# bracelet.net
KiCad netlist of a schematic drawn in EAGLE
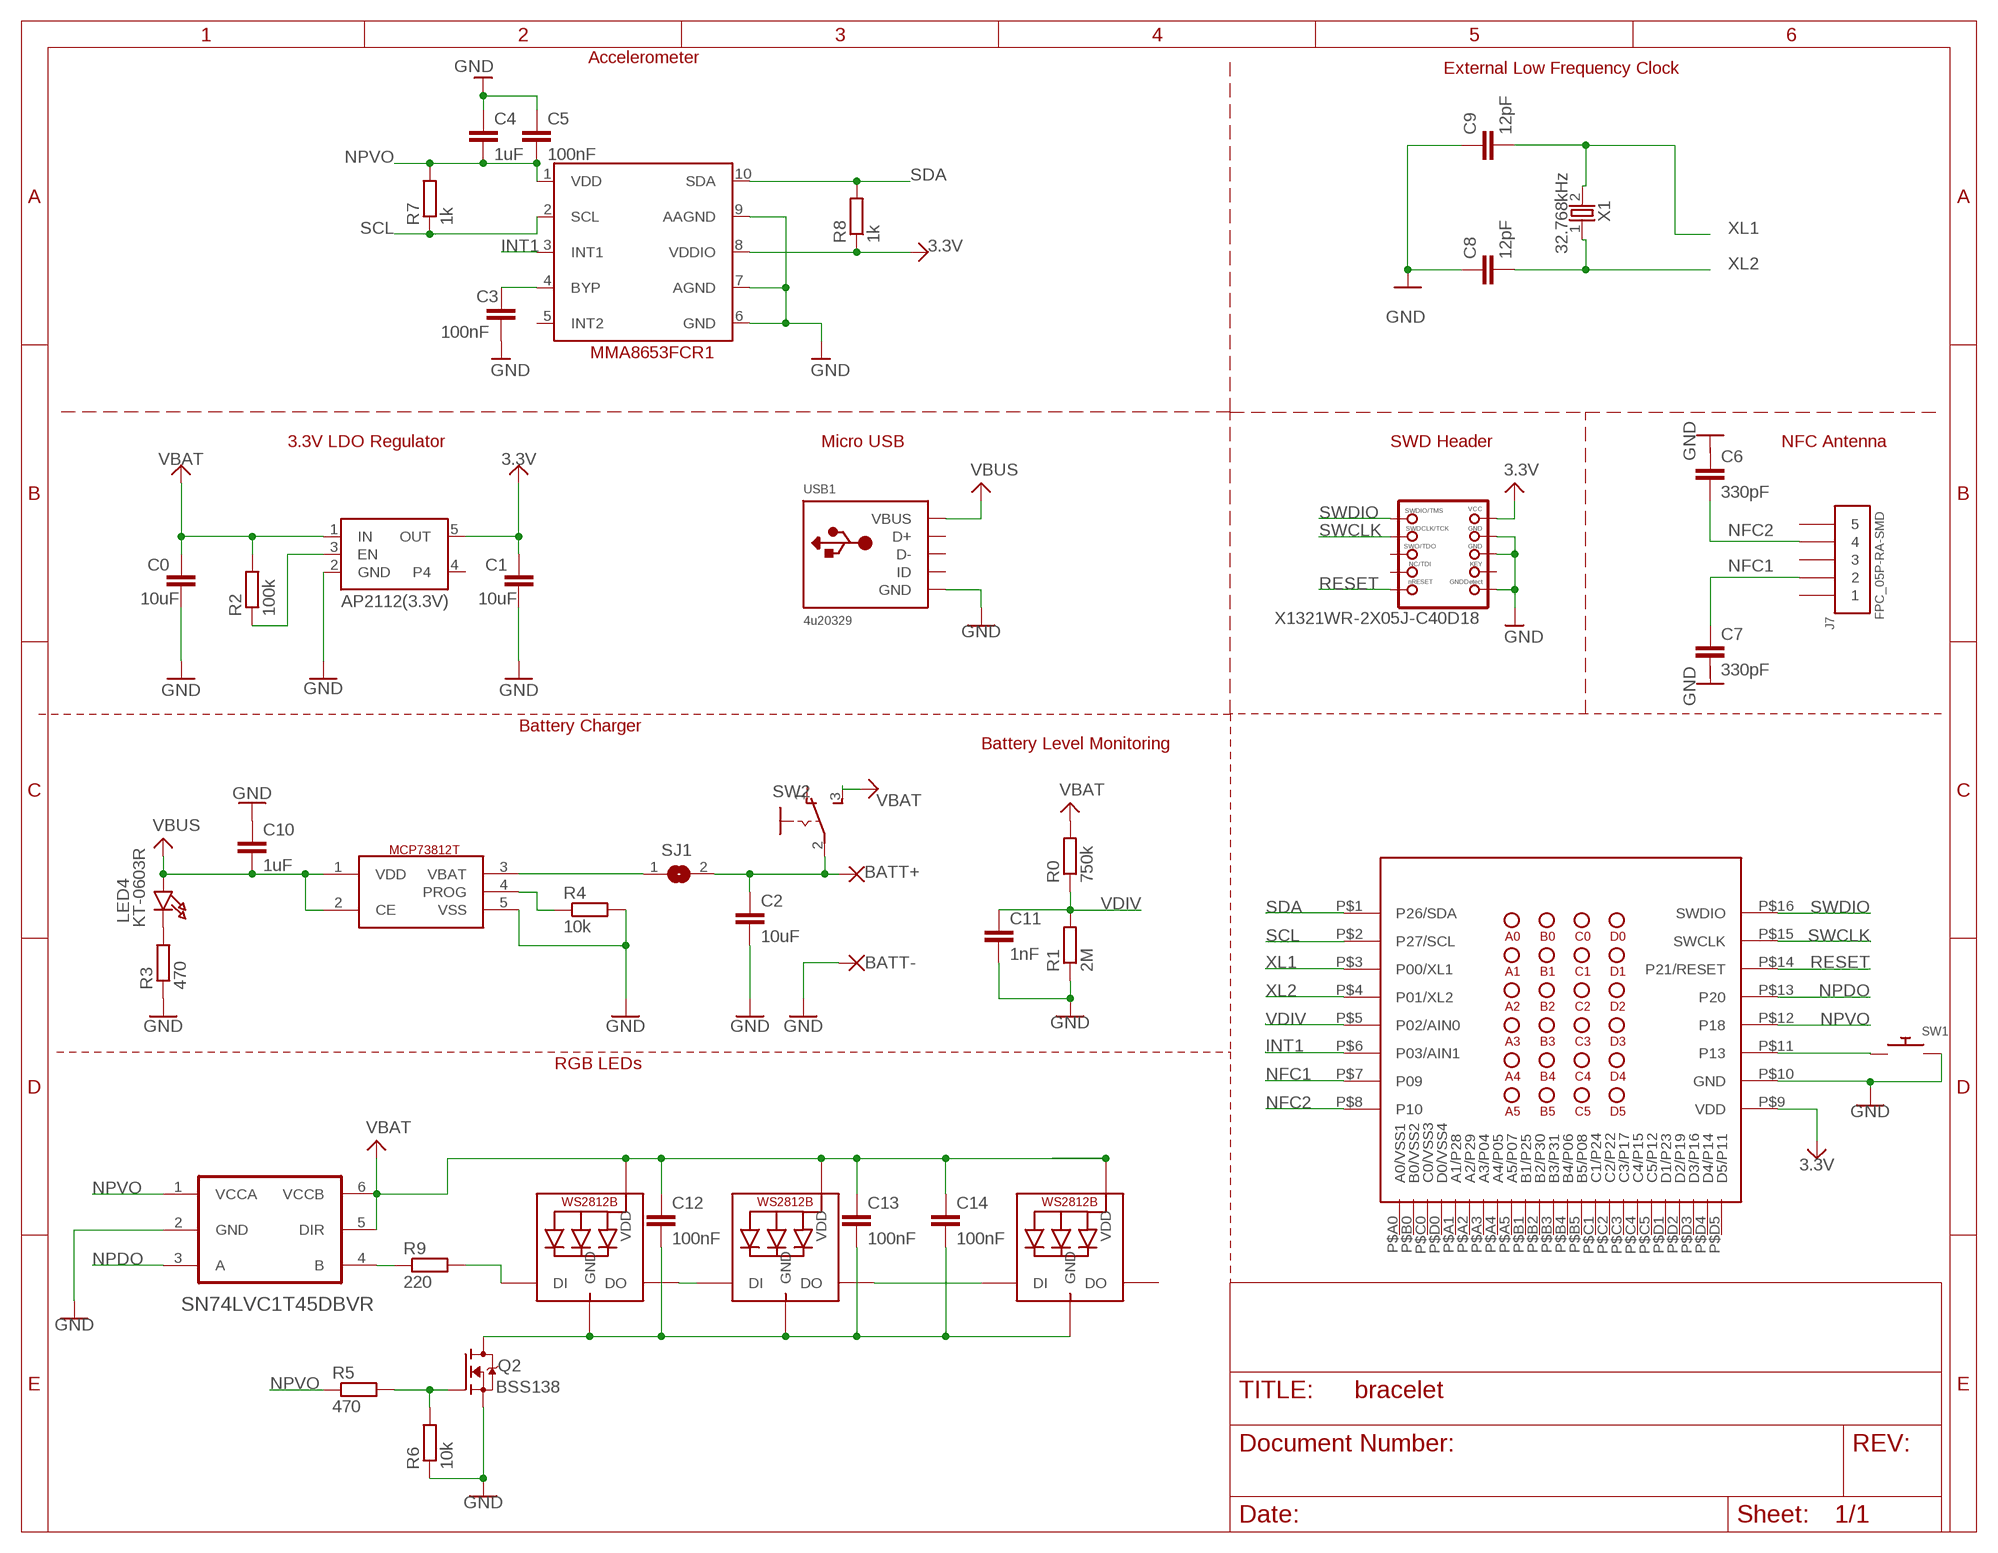
[diagram p0: schematic, sheet 1]

(export (version "E")
  (design (tool "Eeschema 10.0.6"))
  (components
    (comp (ref "BATT+")
      (value "WIREPADSMD2,54-5,08")
      (footprint "eagle-import:SMD2,54-5,08")
      (libsource (lib "eagle-import") (part "WIREPADSMD2,54-5,08"))
    )
    (comp (ref "BATT-")
      (value "WIREPADSMD2,54-5,08")
      (footprint "eagle-import:SMD2,54-5,08")
      (libsource (lib "eagle-import") (part "WIREPADSMD2,54-5,08"))
    )
    (comp (ref "C0")
      (value "10uF")
      (footprint "eagle-import:RESC0402_N")
      (libsource (lib "eagle-import") (part "CAPACITOR_0402_N"))
    )
    (comp (ref "C1")
      (value "10uF")
      (footprint "eagle-import:RESC0402_N")
      (libsource (lib "eagle-import") (part "CAPACITOR_0402_N"))
    )
    (comp (ref "C2")
      (value "10uF")
      (footprint "eagle-import:C0402")
      (libsource (lib "eagle-import") (part "C-EUC0402"))
    )
    (comp (ref "C3")
      (value "100nF")
      (footprint "eagle-import:C0402")
      (libsource (lib "eagle-import") (part "C-EUC0402"))
    )
    (comp (ref "C4")
      (value "1uF")
      (footprint "eagle-import:C0402")
      (libsource (lib "eagle-import") (part "C-EUC0402"))
    )
    (comp (ref "C5")
      (value "100nF")
      (footprint "eagle-import:C0402")
      (libsource (lib "eagle-import") (part "C-EUC0402"))
    )
    (comp (ref "C6")
      (value "330pF")
      (footprint "eagle-import:C0402")
      (libsource (lib "eagle-import") (part "C-EUC0402"))
    )
    (comp (ref "C7")
      (value "330pF")
      (footprint "eagle-import:C0402")
      (libsource (lib "eagle-import") (part "C-EUC0402"))
    )
    (comp (ref "C8")
      (value "12pF")
      (footprint "eagle-import:C0402")
      (libsource (lib "eagle-import") (part "C-EUC0402"))
    )
    (comp (ref "C9")
      (value "12pF")
      (footprint "eagle-import:C0402")
      (libsource (lib "eagle-import") (part "C-EUC0402"))
    )
    (comp (ref "C10")
      (value "1uF")
      (footprint "eagle-import:C0402")
      (libsource (lib "eagle-import") (part "C-EUC0402"))
    )
    (comp (ref "C11")
      (value "1nF")
      (footprint "eagle-import:C0402")
      (libsource (lib "eagle-import") (part "C-EUC0402"))
    )
    (comp (ref "C12")
      (value "100nF")
      (footprint "eagle-import:C0402")
      (libsource (lib "eagle-import") (part "C-EUC0402"))
    )
    (comp (ref "C13")
      (value "100nF")
      (footprint "eagle-import:C0402")
      (libsource (lib "eagle-import") (part "C-EUC0402"))
    )
    (comp (ref "C14")
      (value "100nF")
      (footprint "eagle-import:C0402")
      (libsource (lib "eagle-import") (part "C-EUC0402"))
    )
    (comp (ref "J1")
      (value "X1321WR-2X05J-C40D18")
      (footprint "eagle-import:2X05_1.27MM_BOX_POSTS")
      (libsource (lib "eagle-import") (part "JTAG-CORTEXBOXPOSTS"))
    )
    (comp (ref "J7")
      (value "FPC_05P-RA-SMD")
      (footprint "eagle-import:FPC_05P-RA-SMD")
      (libsource (lib "eagle-import") (part "FPC_05P-RA-SMD"))
    )
    (comp (ref "LED1")
      (value "WS2812B5050")
      (footprint "eagle-import:WS2812B")
      (fields (field (name "MF") "Worldsemi") (field (name "MP") "WS2812B"))
      (libsource (lib "eagle-import") (part "WS2812B5050"))
    )
    (comp (ref "LED2")
      (value "WS2812B5050")
      (footprint "eagle-import:WS2812B")
      (fields (field (name "MF") "Worldsemi") (field (name "MP") "WS2812B"))
      (libsource (lib "eagle-import") (part "WS2812B5050"))
    )
    (comp (ref "LED3")
      (value "WS2812B5050")
      (footprint "eagle-import:WS2812B")
      (fields (field (name "MF") "Worldsemi") (field (name "MP") "WS2812B"))
      (libsource (lib "eagle-import") (part "WS2812B5050"))
    )
    (comp (ref "LED4")
      (value "LED0805_NOOUTLINE")
      (footprint "eagle-import:CHIPLED_0805_NOOUTLINE")
      (libsource (lib "eagle-import") (part "LED0805_NOOUTLINE"))
    )
    (comp (ref "MMA8653FCR1")
      (value "MMA8653FCR1")
      (footprint "eagle-import:MMA8653FCR1")
      (fields (field (name "MF") "NXP Semiconductors"))
      (libsource (lib "eagle-import") (part "MMA8653FCR1"))
    )
    (comp (ref "Q2")
      (value "BSS138")
      (footprint "eagle-import:SOT95P240X111-3N")
      (fields (field (name "MF") "ON Semiconductor"))
      (libsource (lib "eagle-import") (part "BSS138"))
    )
    (comp (ref "R0")
      (value "750k")
      (footprint "eagle-import:R0603")
      (libsource (lib "eagle-import") (part "rcl_334_R-EU_R0603"))
    )
    (comp (ref "R1")
      (value "2M")
      (footprint "eagle-import:R0603")
      (libsource (lib "eagle-import") (part "rcl_334_R-EU_R0603"))
    )
    (comp (ref "R2")
      (value "100k")
      (footprint "eagle-import:R0402")
      (libsource (lib "eagle-import") (part "R-EU_R0402"))
    )
    (comp (ref "R3")
      (value "470")
      (footprint "eagle-import:R0402")
      (libsource (lib "eagle-import") (part "R-EU_R0402"))
    )
    (comp (ref "R4")
      (value "10k")
      (footprint "eagle-import:R0402")
      (libsource (lib "eagle-import") (part "R-EU_R0402"))
    )
    (comp (ref "R5")
      (value "470")
      (footprint "eagle-import:R0402")
      (libsource (lib "eagle-import") (part "R-EU_R0402"))
    )
    (comp (ref "R6")
      (value "10k")
      (footprint "eagle-import:R0402")
      (libsource (lib "eagle-import") (part "R-EU_R0402"))
    )
    (comp (ref "R7")
      (value "1k")
      (footprint "eagle-import:R0402")
      (libsource (lib "eagle-import") (part "R-EU_R0402"))
    )
    (comp (ref "R8")
      (value "1k")
      (footprint "eagle-import:R0402")
      (libsource (lib "eagle-import") (part "R-EU_R0402"))
    )
    (comp (ref "R9")
      (value "220")
      (footprint "eagle-import:R0402")
      (libsource (lib "eagle-import") (part "R-EU_R0402"))
    )
    (comp (ref "SJ1") (value "SJ") (footprint "eagle-import:SJ") (libsource (lib "eagle-import") (part "SJ")))
    (comp (ref "SW1")
      (value "SWITCH_PUSHBUTTONSOFTTOUCHSMD_SJ")
      (footprint "eagle-import:PUSHBUTTON_SMD_SJ")
      (libsource (lib "eagle-import") (part "SWITCH_PUSHBUTTONSOFTTOUCHSMD_SJ"))
    )
    (comp (ref "SW2")
      (value "255SB")
      (footprint "eagle-import:255SB")
      (libsource (lib "eagle-import") (part "255SB"))
    )
    (comp (ref "U$5")
      (value "MCP73812T-420I/OT")
      (footprint "eagle-import:MCP73812T-420I_OT")
      (libsource (lib "eagle-import") (part "MCP73812T-420I/OT"))
    )
    (comp (ref "U1")
      (value "BT832L")
      (footprint "eagle-import:BT832L")
      (libsource (lib "eagle-import") (part "BT832L"))
    )
    (comp (ref "U2")
      (value "SN74LVC1T45DBVR")
      (footprint "eagle-import:SOT95P280X145-6N")
      (fields (field (name "MF") "Texas Instruments"))
      (libsource (lib "eagle-import") (part "SN74LVC1T45DBVR"))
    )
    (comp (ref "U3")
      (value "AP2112(3.3V)")
      (footprint "eagle-import:SOT23-5")
      (libsource (lib "eagle-import") (part "VREG_SOT23-5"))
    )
    (comp (ref "USB1")
      (value "4u20329")
      (footprint "eagle-import:4UCONN_20329_V2")
      (libsource (lib "eagle-import") (part "USB_MICRO_20329_V2"))
    )
    (comp (ref "X1")
      (value "32.768kHz")
      (footprint "eagle-import:XTAL_3215_N")
      (libsource (lib "eagle-import") (part "XTAL_32KHZ"))
    )
  )
  (nets
    (net (code "1") (name "/INT1") (class "Default")
      (node (ref "MMA8653FCR1") (pin "3") (pinfunction "INT1_3") (pintype "bidirectional"))
      (node (ref "U1") (pin "P$6") (pinfunction "P03/AIN1_P$6") (pintype "bidirectional"))
    )
    (net (code "2") (name "/NFC1") (class "Default")
      (node (ref "C7") (pin "1") (pinfunction "1_1") (pintype "passive"))
      (node (ref "J7") (pin "2") (pinfunction "2_2") (pintype "bidirectional"))
      (node (ref "U1") (pin "P$7") (pinfunction "P09_P$7") (pintype "bidirectional"))
    )
    (net (code "3") (name "/NFC2") (class "Default")
      (node (ref "C6") (pin "2") (pinfunction "2_2") (pintype "passive"))
      (node (ref "J7") (pin "4") (pinfunction "4_4") (pintype "bidirectional"))
      (node (ref "U1") (pin "P$8") (pinfunction "P10_P$8") (pintype "bidirectional"))
    )
    (net (code "4") (name "/NPDO") (class "Default")
      (node (ref "U1") (pin "P$13") (pinfunction "P20_P$13") (pintype "bidirectional"))
      (node (ref "U2") (pin "3") (pinfunction "A_3") (pintype "input"))
    )
    (net (code "5") (name "/NPVO") (class "Default")
      (node (ref "C4") (pin "2") (pinfunction "2_2") (pintype "passive"))
      (node (ref "C5") (pin "2") (pinfunction "2_2") (pintype "passive"))
      (node (ref "MMA8653FCR1") (pin "1") (pinfunction "VDD_1") (pintype "bidirectional"))
      (node (ref "R5") (pin "1") (pinfunction "1_1") (pintype "passive"))
      (node (ref "R7") (pin "2") (pinfunction "2_2") (pintype "passive"))
      (node (ref "U1") (pin "P$12") (pinfunction "P18_P$12") (pintype "bidirectional"))
      (node (ref "U2") (pin "1") (pinfunction "VCCA_1") (pintype "power_in"))
    )
    (net (code "6") (name "/RESET") (class "Default")
      (node (ref "J1") (pin "10") (pinfunction "NRESET_10") (pintype "bidirectional"))
      (node (ref "U1") (pin "P$14") (pinfunction "P21/RESET_P$14") (pintype "bidirectional"))
    )
    (net (code "7") (name "/SCL") (class "Default")
      (node (ref "MMA8653FCR1") (pin "2") (pinfunction "SCL_2") (pintype "bidirectional"))
      (node (ref "R7") (pin "1") (pinfunction "1_1") (pintype "passive"))
      (node (ref "U1") (pin "P$2") (pinfunction "P27/SCL_P$2") (pintype "bidirectional"))
    )
    (net (code "8") (name "/SDA") (class "Default")
      (node (ref "MMA8653FCR1") (pin "10") (pinfunction "SDA_10") (pintype "bidirectional"))
      (node (ref "R8") (pin "2") (pinfunction "2_2") (pintype "passive"))
      (node (ref "U1") (pin "P$1") (pinfunction "P26/SDA_P$1") (pintype "bidirectional"))
    )
    (net (code "9") (name "/SWCLK") (class "Default")
      (node (ref "J1") (pin "4") (pinfunction "SWDCLK_4") (pintype "bidirectional"))
      (node (ref "U1") (pin "P$15") (pinfunction "SWCLK_P$15") (pintype "bidirectional"))
    )
    (net (code "10") (name "/SWDIO") (class "Default")
      (node (ref "J1") (pin "2") (pinfunction "SWDIO_2") (pintype "bidirectional"))
      (node (ref "U1") (pin "P$16") (pinfunction "SWDIO_P$16") (pintype "bidirectional"))
    )
    (net (code "11") (name "/VDIV") (class "Default")
      (node (ref "C11") (pin "1") (pinfunction "1_1") (pintype "passive"))
      (node (ref "R0") (pin "1") (pinfunction "1_1") (pintype "passive"))
      (node (ref "R1") (pin "2") (pinfunction "2_2") (pintype "passive"))
      (node (ref "U1") (pin "P$5") (pinfunction "P02/AIN0_P$5") (pintype "bidirectional"))
    )
    (net (code "12") (name "/XL1") (class "Default")
      (node (ref "C9") (pin "2") (pinfunction "2_2") (pintype "passive"))
      (node (ref "U1") (pin "P$3") (pinfunction "P00/XL1_P$3") (pintype "bidirectional"))
      (node (ref "X1") (pin "2") (pinfunction "2_2") (pintype "passive"))
    )
    (net (code "13") (name "/XL2") (class "Default")
      (node (ref "C8") (pin "2") (pinfunction "2_2") (pintype "passive"))
      (node (ref "U1") (pin "P$4") (pinfunction "P01/XL2_P$4") (pintype "bidirectional"))
      (node (ref "X1") (pin "1") (pinfunction "1_1") (pintype "passive"))
    )
    (net (code "14") (name "3.3V") (class "Default")
      (node (ref "C1") (pin "1") (pinfunction "1_1") (pintype "passive"))
      (node (ref "J1") (pin "1") (pinfunction "VCC_1") (pintype "power_in"))
      (node (ref "MMA8653FCR1") (pin "8") (pinfunction "VDDIO_8") (pintype "bidirectional"))
      (node (ref "R8") (pin "1") (pinfunction "1_1") (pintype "passive"))
      (node (ref "U1") (pin "P$9") (pinfunction "VDD_P$9") (pintype "bidirectional"))
      (node (ref "U3") (pin "5") (pinfunction "OUT_5") (pintype "power_in"))
    )
    (net (code "15") (name "GND") (class "Default")
      (node (ref "BATT-") (pin "1") (pinfunction "P_1") (pintype "passive"))
      (node (ref "C0") (pin "2") (pinfunction "2_2") (pintype "passive"))
      (node (ref "C1") (pin "2") (pinfunction "2_2") (pintype "passive"))
      (node (ref "C10") (pin "1") (pinfunction "1_1") (pintype "passive"))
      (node (ref "C11") (pin "2") (pinfunction "2_2") (pintype "passive"))
      (node (ref "C2") (pin "2") (pinfunction "2_2") (pintype "passive"))
      (node (ref "C3") (pin "2") (pinfunction "2_2") (pintype "passive"))
      (node (ref "C4") (pin "1") (pinfunction "1_1") (pintype "passive"))
      (node (ref "C5") (pin "1") (pinfunction "1_1") (pintype "passive"))
      (node (ref "C8") (pin "1") (pinfunction "1_1") (pintype "passive"))
      (node (ref "C9") (pin "1") (pinfunction "1_1") (pintype "passive"))
      (node (ref "J1") (pin "3") (pinfunction "GND_3") (pintype "power_in"))
      (node (ref "J1") (pin "5") (pinfunction "GND_5") (pintype "power_in"))
      (node (ref "J1") (pin "9") (pinfunction "GNDDETECT_9") (pintype "bidirectional"))
      (node (ref "MMA8653FCR1") (pin "6") (pinfunction "GND_6") (pintype "bidirectional"))
      (node (ref "MMA8653FCR1") (pin "7") (pinfunction "AGND_7") (pintype "bidirectional"))
      (node (ref "MMA8653FCR1") (pin "9") (pinfunction "AAGND_9") (pintype "bidirectional"))
      (node (ref "Q2") (pin "2") (pinfunction "S_2") (pintype "passive"))
      (node (ref "R1") (pin "1") (pinfunction "1_1") (pintype "passive"))
      (node (ref "R3") (pin "1") (pinfunction "1_1") (pintype "passive"))
      (node (ref "R4") (pin "2") (pinfunction "2_2") (pintype "passive"))
      (node (ref "R6") (pin "1") (pinfunction "1_1") (pintype "passive"))
      (node (ref "SW1") (pin "P$2") (pinfunction "P$2_P$2") (pintype "passive"))
      (node (ref "U$5") (pin "5") (pinfunction "VSS_5") (pintype "bidirectional"))
      (node (ref "U1") (pin "P$10") (pinfunction "GND_P$10") (pintype "bidirectional"))
      (node (ref "U2") (pin "2") (pinfunction "GND_2") (pintype "power_in"))
      (node (ref "U3") (pin "2") (pinfunction "GND_2") (pintype "power_in"))
      (node (ref "USB1") (pin "BASE@1") (pinfunction "GND_BASE@1") (pintype "power_in"))
      (node (ref "USB1") (pin "BASE@2") (pinfunction "GND_BASE@2") (pintype "power_in"))
      (node (ref "USB1") (pin "GND") (pinfunction "GND_GND") (pintype "power_in"))
      (node (ref "USB1") (pin "SPRT@1") (pinfunction "GND_SPRT@1") (pintype "power_in"))
      (node (ref "USB1") (pin "SPRT@2") (pinfunction "GND_SPRT@2") (pintype "power_in"))
      (node (ref "USB1") (pin "SPRT@3") (pinfunction "GND_SPRT@3") (pintype "power_in"))
      (node (ref "USB1") (pin "SPRT@4") (pinfunction "GND_SPRT@4") (pintype "power_in"))
    )
    (net (code "16") (name "Net-(BATT+-P)") (class "Default")
      (node (ref "BATT+") (pin "1") (pinfunction "P_1") (pintype "passive"))
      (node (ref "C2") (pin "1") (pinfunction "1_1") (pintype "passive"))
      (node (ref "SJ1") (pin "2") (pinfunction "2_2") (pintype "passive"))
      (node (ref "SW2") (pin "2") (pinfunction "P_2") (pintype "passive"))
    )
    (net (code "17") (name "Net-(LED1-DI)") (class "Default")
      (node (ref "LED1") (pin "4-DIN") (pinfunction "DI_4-DIN") (pintype "input"))
      (node (ref "R9") (pin "2") (pinfunction "2_2") (pintype "passive"))
    )
    (net (code "18") (name "Net-(LED1-DO)") (class "Default")
      (node (ref "LED1") (pin "2-DOUT") (pinfunction "DO_2-DOUT") (pintype "output"))
      (node (ref "LED2") (pin "4-DIN") (pinfunction "DI_4-DIN") (pintype "input"))
    )
    (net (code "19") (name "Net-(LED1-GND)") (class "Default")
      (node (ref "C12") (pin "2") (pinfunction "2_2") (pintype "passive"))
      (node (ref "C13") (pin "2") (pinfunction "2_2") (pintype "passive"))
      (node (ref "C14") (pin "2") (pinfunction "2_2") (pintype "passive"))
      (node (ref "LED1") (pin "3-GND") (pinfunction "GND_3-GND") (pintype "power_in"))
      (node (ref "LED2") (pin "3-GND") (pinfunction "GND_3-GND") (pintype "power_in"))
      (node (ref "LED3") (pin "3-GND") (pinfunction "GND_3-GND") (pintype "power_in"))
      (node (ref "Q2") (pin "3") (pinfunction "D_3") (pintype "passive"))
    )
    (net (code "20") (name "Net-(LED2-DO)") (class "Default")
      (node (ref "LED2") (pin "2-DOUT") (pinfunction "DO_2-DOUT") (pintype "output"))
      (node (ref "LED3") (pin "4-DIN") (pinfunction "DI_4-DIN") (pintype "input"))
    )
    (net (code "21") (name "Net-(LED4-PadC)") (class "Default")
      (node (ref "LED4") (pin "C") (pinfunction "C_C") (pintype "passive"))
      (node (ref "R3") (pin "2") (pinfunction "2_2") (pintype "passive"))
    )
    (net (code "22") (name "Net-(MMA8653FCR1-BYP)") (class "Default")
      (node (ref "C3") (pin "1") (pinfunction "1_1") (pintype "passive"))
      (node (ref "MMA8653FCR1") (pin "4") (pinfunction "BYP_4") (pintype "bidirectional"))
    )
    (net (code "23") (name "Net-(Q2-G)") (class "Default")
      (node (ref "Q2") (pin "1") (pinfunction "G_1") (pintype "passive"))
      (node (ref "R5") (pin "2") (pinfunction "2_2") (pintype "passive"))
      (node (ref "R6") (pin "2") (pinfunction "2_2") (pintype "passive"))
    )
    (net (code "24") (name "Net-(U$5-PROG)") (class "Default")
      (node (ref "R4") (pin "1") (pinfunction "1_1") (pintype "passive"))
      (node (ref "U$5") (pin "4") (pinfunction "PROG_4") (pintype "bidirectional"))
    )
    (net (code "25") (name "Net-(U$5-VBAT)") (class "Default")
      (node (ref "SJ1") (pin "1") (pinfunction "1_1") (pintype "passive"))
      (node (ref "U$5") (pin "3") (pinfunction "VBAT_3") (pintype "bidirectional"))
    )
    (net (code "26") (name "Net-(U1-P13)") (class "Default")
      (node (ref "SW1") (pin "P$1") (pinfunction "P$1_P$1") (pintype "passive"))
      (node (ref "U1") (pin "P$11") (pinfunction "P13_P$11") (pintype "bidirectional"))
    )
    (net (code "27") (name "Net-(U2-B)") (class "Default")
      (node (ref "R9") (pin "1") (pinfunction "1_1") (pintype "passive"))
      (node (ref "U2") (pin "4") (pinfunction "B_4") (pintype "output"))
    )
    (net (code "28") (name "Net-(U3-EN)") (class "Default")
      (node (ref "R2") (pin "1") (pinfunction "1_1") (pintype "passive"))
      (node (ref "U3") (pin "3") (pinfunction "EN_3") (pintype "input"))
    )
    (net (code "29") (name "VBAT") (class "Default")
      (node (ref "C0") (pin "1") (pinfunction "1_1") (pintype "passive"))
      (node (ref "C12") (pin "1") (pinfunction "1_1") (pintype "passive"))
      (node (ref "C13") (pin "1") (pinfunction "1_1") (pintype "passive"))
      (node (ref "C14") (pin "1") (pinfunction "1_1") (pintype "passive"))
      (node (ref "LED1") (pin "1-VDD") (pinfunction "VDD_1-VDD") (pintype "power_in"))
      (node (ref "LED2") (pin "1-VDD") (pinfunction "VDD_1-VDD") (pintype "power_in"))
      (node (ref "LED3") (pin "1-VDD") (pinfunction "VDD_1-VDD") (pintype "power_in"))
      (node (ref "R0") (pin "2") (pinfunction "2_2") (pintype "passive"))
      (node (ref "R2") (pin "2") (pinfunction "2_2") (pintype "passive"))
      (node (ref "SW2") (pin "3") (pinfunction "S_3") (pintype "passive"))
      (node (ref "U2") (pin "5") (pinfunction "DIR_5") (pintype "input"))
      (node (ref "U2") (pin "6") (pinfunction "VCCB_6") (pintype "power_in"))
      (node (ref "U3") (pin "1") (pinfunction "IN_1") (pintype "power_in"))
    )
    (net (code "30") (name "VBUS") (class "Default")
      (node (ref "C10") (pin "2") (pinfunction "2_2") (pintype "passive"))
      (node (ref "LED4") (pin "A") (pinfunction "A_A") (pintype "passive"))
      (node (ref "U$5") (pin "1") (pinfunction "VDD_1") (pintype "bidirectional"))
      (node (ref "U$5") (pin "2") (pinfunction "CE_2") (pintype "bidirectional"))
      (node (ref "USB1") (pin "VBUS") (pinfunction "VBUS_VBUS") (pintype "power_in"))
    )
    (net (code "31") (name "unconnected-(C6-Pad1)") (class "Default")
      (node (ref "C6") (pin "1") (pinfunction "1_1") (pintype "passive"))
    )
    (net (code "32") (name "unconnected-(C7-Pad2)") (class "Default")
      (node (ref "C7") (pin "2") (pinfunction "2_2") (pintype "passive"))
    )
    (net (code "33") (name "unconnected-(J1-KEY-Pad7)") (class "Default")
      (node (ref "J1") (pin "7") (pinfunction "KEY_7") (pintype "bidirectional"))
    )
    (net (code "34") (name "unconnected-(J1-SWO-Pad6)") (class "Default")
      (node (ref "J1") (pin "6") (pinfunction "SWO_6") (pintype "bidirectional"))
    )
    (net (code "35") (name "unconnected-(J1-TDI-Pad8)") (class "Default")
      (node (ref "J1") (pin "8") (pinfunction "TDI_8") (pintype "bidirectional"))
    )
    (net (code "36") (name "unconnected-(J7-Pad1)") (class "Default")
      (node (ref "J7") (pin "1") (pinfunction "1_1") (pintype "bidirectional"))
    )
    (net (code "37") (name "unconnected-(J7-Pad3)") (class "Default")
      (node (ref "J7") (pin "3") (pinfunction "3_3") (pintype "bidirectional"))
    )
    (net (code "38") (name "unconnected-(J7-Pad5)") (class "Default")
      (node (ref "J7") (pin "5") (pinfunction "5_5") (pintype "bidirectional"))
    )
    (net (code "39") (name "unconnected-(LED3-DO-Pad2-DOUT)") (class "Default")
      (node (ref "LED3") (pin "2-DOUT") (pinfunction "DO_2-DOUT") (pintype "output"))
    )
    (net (code "40") (name "unconnected-(MMA8653FCR1-INT2-Pad5)") (class "Default")
      (node (ref "MMA8653FCR1") (pin "5") (pinfunction "INT2_5") (pintype "bidirectional"))
    )
    (net (code "41") (name "unconnected-(SW2-O-Pad1)") (class "Default")
      (node (ref "SW2") (pin "1") (pinfunction "O_1") (pintype "passive"))
    )
    (net (code "42") (name "unconnected-(U1-A0{slash}VSS1-PadP$A0)") (class "Default")
      (node (ref "U1") (pin "P$A0") (pinfunction "A0/VSS1_P$A0") (pintype "bidirectional"))
    )
    (net (code "43") (name "unconnected-(U1-A1{slash}P28-PadP$A1)") (class "Default")
      (node (ref "U1") (pin "P$A1") (pinfunction "A1/P28_P$A1") (pintype "bidirectional"))
    )
    (net (code "44") (name "unconnected-(U1-A2{slash}P29-PadP$A2)") (class "Default")
      (node (ref "U1") (pin "P$A2") (pinfunction "A2/P29_P$A2") (pintype "bidirectional"))
    )
    (net (code "45") (name "unconnected-(U1-A3{slash}P04-PadP$A3)") (class "Default")
      (node (ref "U1") (pin "P$A3") (pinfunction "A3/P04_P$A3") (pintype "bidirectional"))
    )
    (net (code "46") (name "unconnected-(U1-A4{slash}P05-PadP$A4)") (class "Default")
      (node (ref "U1") (pin "P$A4") (pinfunction "A4/P05_P$A4") (pintype "bidirectional"))
    )
    (net (code "47") (name "unconnected-(U1-A5{slash}P07-PadP$A5)") (class "Default")
      (node (ref "U1") (pin "P$A5") (pinfunction "A5/P07_P$A5") (pintype "bidirectional"))
    )
    (net (code "48") (name "unconnected-(U1-B0{slash}VSS2-PadP$B0)") (class "Default")
      (node (ref "U1") (pin "P$B0") (pinfunction "B0/VSS2_P$B0") (pintype "bidirectional"))
    )
    (net (code "49") (name "unconnected-(U1-B1{slash}P25-PadP$B1)") (class "Default")
      (node (ref "U1") (pin "P$B1") (pinfunction "B1/P25_P$B1") (pintype "bidirectional"))
    )
    (net (code "50") (name "unconnected-(U1-B2{slash}P30-PadP$B2)") (class "Default")
      (node (ref "U1") (pin "P$B2") (pinfunction "B2/P30_P$B2") (pintype "bidirectional"))
    )
    (net (code "51") (name "unconnected-(U1-B3{slash}P31-PadP$B3)") (class "Default")
      (node (ref "U1") (pin "P$B3") (pinfunction "B3/P31_P$B3") (pintype "bidirectional"))
    )
    (net (code "52") (name "unconnected-(U1-B4{slash}P06-PadP$B4)") (class "Default")
      (node (ref "U1") (pin "P$B4") (pinfunction "B4/P06_P$B4") (pintype "bidirectional"))
    )
    (net (code "53") (name "unconnected-(U1-B5{slash}P08-PadP$B5)") (class "Default")
      (node (ref "U1") (pin "P$B5") (pinfunction "B5/P08_P$B5") (pintype "bidirectional"))
    )
    (net (code "54") (name "unconnected-(U1-C0{slash}VSS3-PadP$C0)") (class "Default")
      (node (ref "U1") (pin "P$C0") (pinfunction "C0/VSS3_P$C0") (pintype "bidirectional"))
    )
    (net (code "55") (name "unconnected-(U1-C1{slash}P24-PadP$C1)") (class "Default")
      (node (ref "U1") (pin "P$C1") (pinfunction "C1/P24_P$C1") (pintype "bidirectional"))
    )
    (net (code "56") (name "unconnected-(U1-C2{slash}P22-PadP$C2)") (class "Default")
      (node (ref "U1") (pin "P$C2") (pinfunction "C2/P22_P$C2") (pintype "bidirectional"))
    )
    (net (code "57") (name "unconnected-(U1-C3{slash}P17-PadP$C3)") (class "Default")
      (node (ref "U1") (pin "P$C3") (pinfunction "C3/P17_P$C3") (pintype "bidirectional"))
    )
    (net (code "58") (name "unconnected-(U1-C4{slash}P15-PadP$C4)") (class "Default")
      (node (ref "U1") (pin "P$C4") (pinfunction "C4/P15_P$C4") (pintype "bidirectional"))
    )
    (net (code "59") (name "unconnected-(U1-C5{slash}P12-PadP$C5)") (class "Default")
      (node (ref "U1") (pin "P$C5") (pinfunction "C5/P12_P$C5") (pintype "bidirectional"))
    )
    (net (code "60") (name "unconnected-(U1-D0{slash}VSS4-PadP$D0)") (class "Default")
      (node (ref "U1") (pin "P$D0") (pinfunction "D0/VSS4_P$D0") (pintype "bidirectional"))
    )
    (net (code "61") (name "unconnected-(U1-D1{slash}P23-PadP$D1)") (class "Default")
      (node (ref "U1") (pin "P$D1") (pinfunction "D1/P23_P$D1") (pintype "bidirectional"))
    )
    (net (code "62") (name "unconnected-(U1-D2{slash}P19-PadP$D2)") (class "Default")
      (node (ref "U1") (pin "P$D2") (pinfunction "D2/P19_P$D2") (pintype "bidirectional"))
    )
    (net (code "63") (name "unconnected-(U1-D3{slash}P16-PadP$D3)") (class "Default")
      (node (ref "U1") (pin "P$D3") (pinfunction "D3/P16_P$D3") (pintype "bidirectional"))
    )
    (net (code "64") (name "unconnected-(U1-D4{slash}P14-PadP$D4)") (class "Default")
      (node (ref "U1") (pin "P$D4") (pinfunction "D4/P14_P$D4") (pintype "bidirectional"))
    )
    (net (code "65") (name "unconnected-(U1-D5{slash}P11-PadP$D5)") (class "Default")
      (node (ref "U1") (pin "P$D5") (pinfunction "D5/P11_P$D5") (pintype "bidirectional"))
    )
    (net (code "66") (name "unconnected-(U3-P4-Pad4)") (class "Default")
      (node (ref "U3") (pin "4") (pinfunction "P4_4") (pintype "bidirectional"))
    )
    (net (code "67") (name "unconnected-(USB1-PadD+)") (class "Default")
      (node (ref "USB1") (pin "D+") (pinfunction "D+_D+") (pintype "bidirectional"))
    )
    (net (code "68") (name "unconnected-(USB1-PadD-)") (class "Default")
      (node (ref "USB1") (pin "D-") (pinfunction "D-_D-") (pintype "bidirectional"))
    )
    (net (code "69") (name "unconnected-(USB1-PadID)") (class "Default")
      (node (ref "USB1") (pin "ID") (pinfunction "ID_ID") (pintype "bidirectional"))
    )
  )
)
